# ESP_Hub.net
KiCad netlist of a schematic drawn in EAGLE
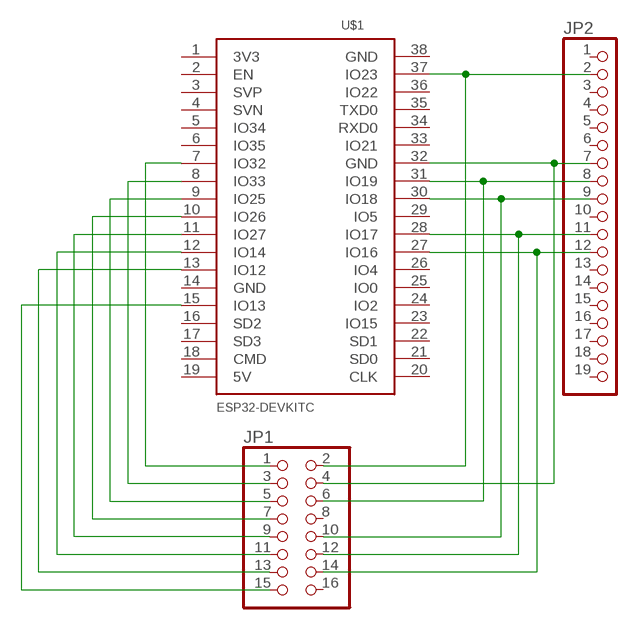
[diagram p0: schematic, sheet 1]

(export (version "E")
  (design (tool "Eeschema 10.0.6"))
  (components
    (comp (ref "JP1")
      (value "PINHD-2X8")
      (footprint "eagle-import:2X08")
      (libsource (lib "eagle-import") (part "PINHD-2X8"))
    )
    (comp (ref "JP2")
      (value "PINHD-1X19")
      (footprint "eagle-import:1X19")
      (libsource (lib "eagle-import") (part "PINHD-1X19"))
    )
    (comp (ref "U$1")
      (value "ESP32DEVKITC")
      (footprint "eagle-import:ESP32-DEVKITC")
      (libsource (lib "eagle-import") (part "ESP32DEVKITC"))
    )
  )
  (nets
    (net (code "1") (name "Net-(JP1-Pad4)") (class "Default")
      (node (ref "JP1") (pin "4") (pinfunction "4_4") (pintype "passive"))
      (node (ref "JP2") (pin "7") (pinfunction "7_7") (pintype "passive"))
      (node (ref "U$1") (pin "32") (pinfunction "GND_32") (pintype "bidirectional"))
    )
    (net (code "2") (name "Net-(U$1-IO12)") (class "Default")
      (node (ref "JP1") (pin "13") (pinfunction "13_13") (pintype "passive"))
      (node (ref "U$1") (pin "13") (pinfunction "IO12_13") (pintype "bidirectional"))
    )
    (net (code "3") (name "Net-(U$1-IO13)") (class "Default")
      (node (ref "JP1") (pin "15") (pinfunction "15_15") (pintype "passive"))
      (node (ref "U$1") (pin "15") (pinfunction "IO13_15") (pintype "bidirectional"))
    )
    (net (code "4") (name "Net-(U$1-IO14)") (class "Default")
      (node (ref "JP1") (pin "11") (pinfunction "11_11") (pintype "passive"))
      (node (ref "U$1") (pin "12") (pinfunction "IO14_12") (pintype "bidirectional"))
    )
    (net (code "5") (name "Net-(U$1-IO16)") (class "Default")
      (node (ref "JP1") (pin "14") (pinfunction "14_14") (pintype "passive"))
      (node (ref "JP2") (pin "12") (pinfunction "12_12") (pintype "passive"))
      (node (ref "U$1") (pin "27") (pinfunction "IO16_27") (pintype "bidirectional"))
    )
    (net (code "6") (name "Net-(U$1-IO17)") (class "Default")
      (node (ref "JP1") (pin "12") (pinfunction "12_12") (pintype "passive"))
      (node (ref "JP2") (pin "11") (pinfunction "11_11") (pintype "passive"))
      (node (ref "U$1") (pin "28") (pinfunction "IO17_28") (pintype "bidirectional"))
    )
    (net (code "7") (name "Net-(U$1-IO18)") (class "Default")
      (node (ref "JP1") (pin "10") (pinfunction "10_10") (pintype "passive"))
      (node (ref "JP2") (pin "9") (pinfunction "9_9") (pintype "passive"))
      (node (ref "U$1") (pin "30") (pinfunction "IO18_30") (pintype "bidirectional"))
    )
    (net (code "8") (name "Net-(U$1-IO19)") (class "Default")
      (node (ref "JP1") (pin "6") (pinfunction "6_6") (pintype "passive"))
      (node (ref "JP2") (pin "8") (pinfunction "8_8") (pintype "passive"))
      (node (ref "U$1") (pin "31") (pinfunction "IO19_31") (pintype "bidirectional"))
    )
    (net (code "9") (name "Net-(U$1-IO23)") (class "Default")
      (node (ref "JP1") (pin "2") (pinfunction "2_2") (pintype "passive"))
      (node (ref "JP2") (pin "2") (pinfunction "2_2") (pintype "passive"))
      (node (ref "U$1") (pin "37") (pinfunction "IO23_37") (pintype "bidirectional"))
    )
    (net (code "10") (name "Net-(U$1-IO25)") (class "Default")
      (node (ref "JP1") (pin "5") (pinfunction "5_5") (pintype "passive"))
      (node (ref "U$1") (pin "9") (pinfunction "IO25_9") (pintype "bidirectional"))
    )
    (net (code "11") (name "Net-(U$1-IO26)") (class "Default")
      (node (ref "JP1") (pin "7") (pinfunction "7_7") (pintype "passive"))
      (node (ref "U$1") (pin "10") (pinfunction "IO26_10") (pintype "bidirectional"))
    )
    (net (code "12") (name "Net-(U$1-IO27)") (class "Default")
      (node (ref "JP1") (pin "9") (pinfunction "9_9") (pintype "passive"))
      (node (ref "U$1") (pin "11") (pinfunction "IO27_11") (pintype "bidirectional"))
    )
    (net (code "13") (name "Net-(U$1-IO32)") (class "Default")
      (node (ref "JP1") (pin "1") (pinfunction "1_1") (pintype "passive"))
      (node (ref "U$1") (pin "7") (pinfunction "IO32_7") (pintype "bidirectional"))
    )
    (net (code "14") (name "Net-(U$1-IO33)") (class "Default")
      (node (ref "JP1") (pin "3") (pinfunction "3_3") (pintype "passive"))
      (node (ref "U$1") (pin "8") (pinfunction "IO33_8") (pintype "bidirectional"))
    )
    (net (code "15") (name "unconnected-(JP1-Pad8)") (class "Default")
      (node (ref "JP1") (pin "8") (pinfunction "8_8") (pintype "passive"))
    )
    (net (code "16") (name "unconnected-(JP1-Pad16)") (class "Default")
      (node (ref "JP1") (pin "16") (pinfunction "16_16") (pintype "passive"))
    )
    (net (code "17") (name "unconnected-(JP2-Pad1)") (class "Default")
      (node (ref "JP2") (pin "1") (pinfunction "1_1") (pintype "passive"))
    )
    (net (code "18") (name "unconnected-(JP2-Pad3)") (class "Default")
      (node (ref "JP2") (pin "3") (pinfunction "3_3") (pintype "passive"))
    )
    (net (code "19") (name "unconnected-(JP2-Pad4)") (class "Default")
      (node (ref "JP2") (pin "4") (pinfunction "4_4") (pintype "passive"))
    )
    (net (code "20") (name "unconnected-(JP2-Pad5)") (class "Default")
      (node (ref "JP2") (pin "5") (pinfunction "5_5") (pintype "passive"))
    )
    (net (code "21") (name "unconnected-(JP2-Pad6)") (class "Default")
      (node (ref "JP2") (pin "6") (pinfunction "6_6") (pintype "passive"))
    )
    (net (code "22") (name "unconnected-(JP2-Pad10)") (class "Default")
      (node (ref "JP2") (pin "10") (pinfunction "10_10") (pintype "passive"))
    )
    (net (code "23") (name "unconnected-(JP2-Pad13)") (class "Default")
      (node (ref "JP2") (pin "13") (pinfunction "13_13") (pintype "passive"))
    )
    (net (code "24") (name "unconnected-(JP2-Pad14)") (class "Default")
      (node (ref "JP2") (pin "14") (pinfunction "14_14") (pintype "passive"))
    )
    (net (code "25") (name "unconnected-(JP2-Pad15)") (class "Default")
      (node (ref "JP2") (pin "15") (pinfunction "15_15") (pintype "passive"))
    )
    (net (code "26") (name "unconnected-(JP2-Pad16)") (class "Default")
      (node (ref "JP2") (pin "16") (pinfunction "16_16") (pintype "passive"))
    )
    (net (code "27") (name "unconnected-(JP2-Pad17)") (class "Default")
      (node (ref "JP2") (pin "17") (pinfunction "17_17") (pintype "passive"))
    )
    (net (code "28") (name "unconnected-(JP2-Pad18)") (class "Default")
      (node (ref "JP2") (pin "18") (pinfunction "18_18") (pintype "passive"))
    )
    (net (code "29") (name "unconnected-(JP2-Pad19)") (class "Default")
      (node (ref "JP2") (pin "19") (pinfunction "19_19") (pintype "passive"))
    )
    (net (code "30") (name "unconnected-(U$1-3V3-Pad1)") (class "Default")
      (node (ref "U$1") (pin "1") (pinfunction "3V3_1") (pintype "bidirectional"))
    )
    (net (code "31") (name "unconnected-(U$1-5V-Pad19)") (class "Default")
      (node (ref "U$1") (pin "19") (pinfunction "5V_19") (pintype "bidirectional"))
    )
    (net (code "32") (name "unconnected-(U$1-CLK-Pad20)") (class "Default")
      (node (ref "U$1") (pin "20") (pinfunction "CLK_20") (pintype "bidirectional"))
    )
    (net (code "33") (name "unconnected-(U$1-CMD-Pad18)") (class "Default")
      (node (ref "U$1") (pin "18") (pinfunction "CMD_18") (pintype "bidirectional"))
    )
    (net (code "34") (name "unconnected-(U$1-EN-Pad2)") (class "Default")
      (node (ref "U$1") (pin "2") (pinfunction "EN_2") (pintype "bidirectional"))
    )
    (net (code "35") (name "unconnected-(U$1-GND-Pad14)") (class "Default")
      (node (ref "U$1") (pin "14") (pinfunction "GND_14") (pintype "bidirectional"))
    )
    (net (code "36") (name "unconnected-(U$1-GND-Pad38)") (class "Default")
      (node (ref "U$1") (pin "38") (pinfunction "GND_38") (pintype "bidirectional"))
    )
    (net (code "37") (name "unconnected-(U$1-IO0-Pad25)") (class "Default")
      (node (ref "U$1") (pin "25") (pinfunction "IO0_25") (pintype "bidirectional"))
    )
    (net (code "38") (name "unconnected-(U$1-IO2-Pad24)") (class "Default")
      (node (ref "U$1") (pin "24") (pinfunction "IO2_24") (pintype "bidirectional"))
    )
    (net (code "39") (name "unconnected-(U$1-IO4-Pad26)") (class "Default")
      (node (ref "U$1") (pin "26") (pinfunction "IO4_26") (pintype "bidirectional"))
    )
    (net (code "40") (name "unconnected-(U$1-IO5-Pad29)") (class "Default")
      (node (ref "U$1") (pin "29") (pinfunction "IO5_29") (pintype "bidirectional"))
    )
    (net (code "41") (name "unconnected-(U$1-IO15-Pad23)") (class "Default")
      (node (ref "U$1") (pin "23") (pinfunction "IO15_23") (pintype "bidirectional"))
    )
    (net (code "42") (name "unconnected-(U$1-IO21-Pad33)") (class "Default")
      (node (ref "U$1") (pin "33") (pinfunction "IO21_33") (pintype "bidirectional"))
    )
    (net (code "43") (name "unconnected-(U$1-IO22-Pad36)") (class "Default")
      (node (ref "U$1") (pin "36") (pinfunction "IO22_36") (pintype "bidirectional"))
    )
    (net (code "44") (name "unconnected-(U$1-IO34-Pad5)") (class "Default")
      (node (ref "U$1") (pin "5") (pinfunction "IO34_5") (pintype "bidirectional"))
    )
    (net (code "45") (name "unconnected-(U$1-IO35-Pad6)") (class "Default")
      (node (ref "U$1") (pin "6") (pinfunction "IO35_6") (pintype "bidirectional"))
    )
    (net (code "46") (name "unconnected-(U$1-RXD0-Pad34)") (class "Default")
      (node (ref "U$1") (pin "34") (pinfunction "RXD0_34") (pintype "bidirectional"))
    )
    (net (code "47") (name "unconnected-(U$1-SD0-Pad21)") (class "Default")
      (node (ref "U$1") (pin "21") (pinfunction "SD0_21") (pintype "bidirectional"))
    )
    (net (code "48") (name "unconnected-(U$1-SD1-Pad22)") (class "Default")
      (node (ref "U$1") (pin "22") (pinfunction "SD1_22") (pintype "bidirectional"))
    )
    (net (code "49") (name "unconnected-(U$1-SD2-Pad16)") (class "Default")
      (node (ref "U$1") (pin "16") (pinfunction "SD2_16") (pintype "bidirectional"))
    )
    (net (code "50") (name "unconnected-(U$1-SD3-Pad17)") (class "Default")
      (node (ref "U$1") (pin "17") (pinfunction "SD3_17") (pintype "bidirectional"))
    )
    (net (code "51") (name "unconnected-(U$1-SVN-Pad4)") (class "Default")
      (node (ref "U$1") (pin "4") (pinfunction "SVN_4") (pintype "bidirectional"))
    )
    (net (code "52") (name "unconnected-(U$1-SVP-Pad3)") (class "Default")
      (node (ref "U$1") (pin "3") (pinfunction "SVP_3") (pintype "bidirectional"))
    )
    (net (code "53") (name "unconnected-(U$1-TXD0-Pad35)") (class "Default")
      (node (ref "U$1") (pin "35") (pinfunction "TXD0_35") (pintype "bidirectional"))
    )
  )
)
